# eCog102_uSD.net
KiCad netlist of a schematic drawn in EAGLE
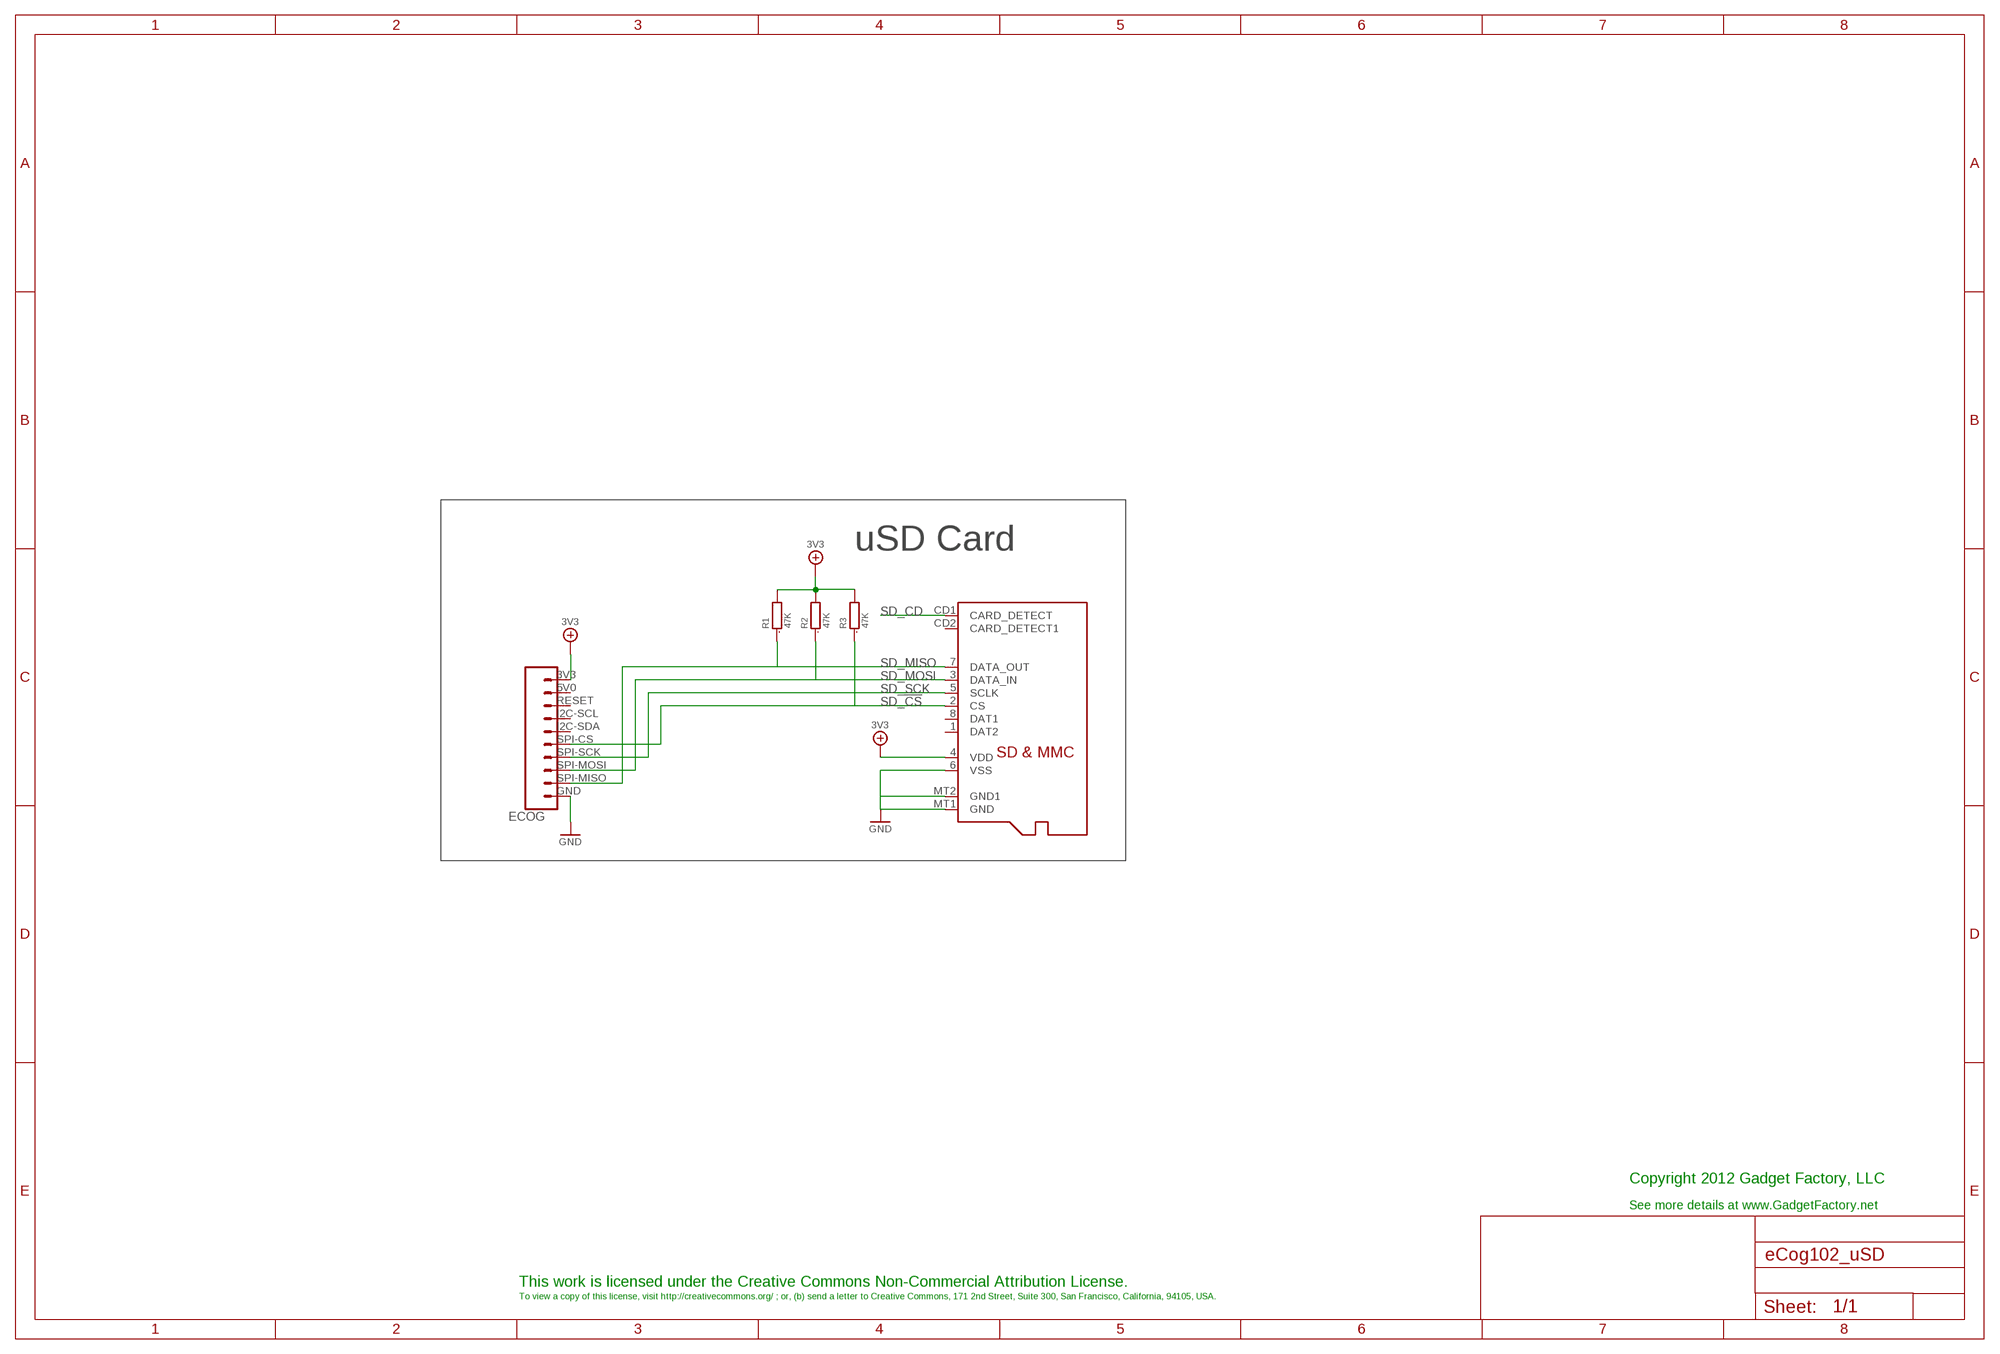
[diagram p0: schematic, sheet 1]

(export (version "E")
  (design (tool "Eeschema 10.0.6"))
  (components
    (comp (ref "ECOG")
      (value "ECOG_BUSES_ROWTHROUGHHOLE")
      (footprint "eagle-import:ECOG_BUSES_TH")
      (libsource (lib "eagle-import") (part "ECOG_BUSES_ROWTHROUGHHOLE"))
    )
    (comp (ref "R1")
      (value "47K")
      (footprint "eagle-import:0805")
      (fields (field (name "PARTNO") "RMCF0805JT47K0"))
      (libsource (lib "eagle-import") (part "R0805"))
    )
    (comp (ref "R2")
      (value "47K")
      (footprint "eagle-import:0805")
      (fields (field (name "PARTNO") "RMCF0805JT47K0"))
      (libsource (lib "eagle-import") (part "R0805"))
    )
    (comp (ref "R3")
      (value "47K")
      (footprint "eagle-import:0805")
      (fields (field (name "PARTNO") "RMCF0805JT47K0"))
      (libsource (lib "eagle-import") (part "R0805"))
    )
    (comp (ref "SD1")
      (value "MICROSD")
      (footprint "eagle-import:MICROSD")
      (fields (field (name "DIGIKEY") "101-00660-68-6-1-ND") (field (name "PARTNO") "101-00660-68-6"))
      (libsource (lib "eagle-import") (part "MICROSD"))
    )
  )
  (nets
    (net (code "1") (name "/SD_CD") (class "Default")
      (node (ref "SD1") (pin "CD1") (pinfunction "CARD_DETECT_CD1") (pintype "passive"))
    )
    (net (code "2") (name "/SD_MISO") (class "Default")
      (node (ref "ECOG") (pin "SPI-MISO") (pinfunction "SPI-MISO_SPI-MISO") (pintype "passive"))
      (node (ref "R1") (pin "1") (pinfunction "1_1") (pintype "passive"))
      (node (ref "SD1") (pin "7") (pinfunction "DATA_OUT_7") (pintype "output"))
    )
    (net (code "3") (name "/SD_MOSI") (class "Default")
      (node (ref "ECOG") (pin "SPI-MOSI") (pinfunction "SPI-MOSI_SPI-MOSI") (pintype "passive"))
      (node (ref "R2") (pin "1") (pinfunction "1_1") (pintype "passive"))
      (node (ref "SD1") (pin "3") (pinfunction "DATA_IN_3") (pintype "input"))
    )
    (net (code "4") (name "/SD_SCK") (class "Default")
      (node (ref "ECOG") (pin "SPI-SCK") (pinfunction "SPI-SCK_SPI-SCK") (pintype "passive"))
      (node (ref "SD1") (pin "5") (pinfunction "SCLK_5") (pintype "input"))
    )
    (net (code "5") (name "/SD_~{CS}") (class "Default")
      (node (ref "ECOG") (pin "SPI-CS") (pinfunction "SPI-CS_SPI-CS") (pintype "passive"))
      (node (ref "R3") (pin "1") (pinfunction "1_1") (pintype "passive"))
      (node (ref "SD1") (pin "2") (pinfunction "CS_2") (pintype "input"))
    )
    (net (code "6") (name "3V3") (class "Default")
      (node (ref "ECOG") (pin "3V3") (pinfunction "3V3_3V3") (pintype "passive"))
      (node (ref "R1") (pin "2") (pinfunction "2_2") (pintype "passive"))
      (node (ref "R2") (pin "2") (pinfunction "2_2") (pintype "passive"))
      (node (ref "R3") (pin "2") (pinfunction "2_2") (pintype "passive"))
      (node (ref "SD1") (pin "4") (pinfunction "VDD_4") (pintype "power_in"))
    )
    (net (code "7") (name "GND") (class "Default")
      (node (ref "ECOG") (pin "GND") (pinfunction "GND_GND") (pintype "passive"))
      (node (ref "SD1") (pin "6") (pinfunction "VSS_6") (pintype "power_in"))
      (node (ref "SD1") (pin "MT1") (pinfunction "GND_MT1") (pintype "power_in"))
      (node (ref "SD1") (pin "MT2") (pinfunction "GND1_MT2") (pintype "power_in"))
    )
    (net (code "8") (name "unconnected-(ECOG-PadI2C-SCL)") (class "Default")
      (node (ref "ECOG") (pin "I2C-SCL") (pinfunction "I2C-SCL_I2C-SCL") (pintype "passive"))
    )
    (net (code "9") (name "unconnected-(ECOG-PadI2C-SDA)") (class "Default")
      (node (ref "ECOG") (pin "I2C-SDA") (pinfunction "I2C-SDA_I2C-SDA") (pintype "passive"))
    )
    (net (code "10") (name "unconnected-(ECOG-RSV-Pad5V0)") (class "Default")
      (node (ref "ECOG") (pin "5V0") (pinfunction "RSV_5V0") (pintype "passive"))
    )
    (net (code "11") (name "unconnected-(ECOG-RSV-PadRESET)") (class "Default")
      (node (ref "ECOG") (pin "RESET") (pinfunction "RSV_RESET") (pintype "passive"))
    )
    (net (code "12") (name "unconnected-(SD1-CARD_DETECT1-PadCD2)") (class "Default")
      (node (ref "SD1") (pin "CD2") (pinfunction "CARD_DETECT1_CD2") (pintype "passive"))
    )
    (net (code "13") (name "unconnected-(SD1-DAT1-Pad8)") (class "Default")
      (node (ref "SD1") (pin "8") (pinfunction "DAT1_8") (pintype "bidirectional"))
    )
    (net (code "14") (name "unconnected-(SD1-DAT2-Pad1)") (class "Default")
      (node (ref "SD1") (pin "1") (pinfunction "DAT2_1") (pintype "bidirectional"))
    )
  )
)
